# poiduino7_7.net
KiCad netlist of a schematic drawn in EAGLE
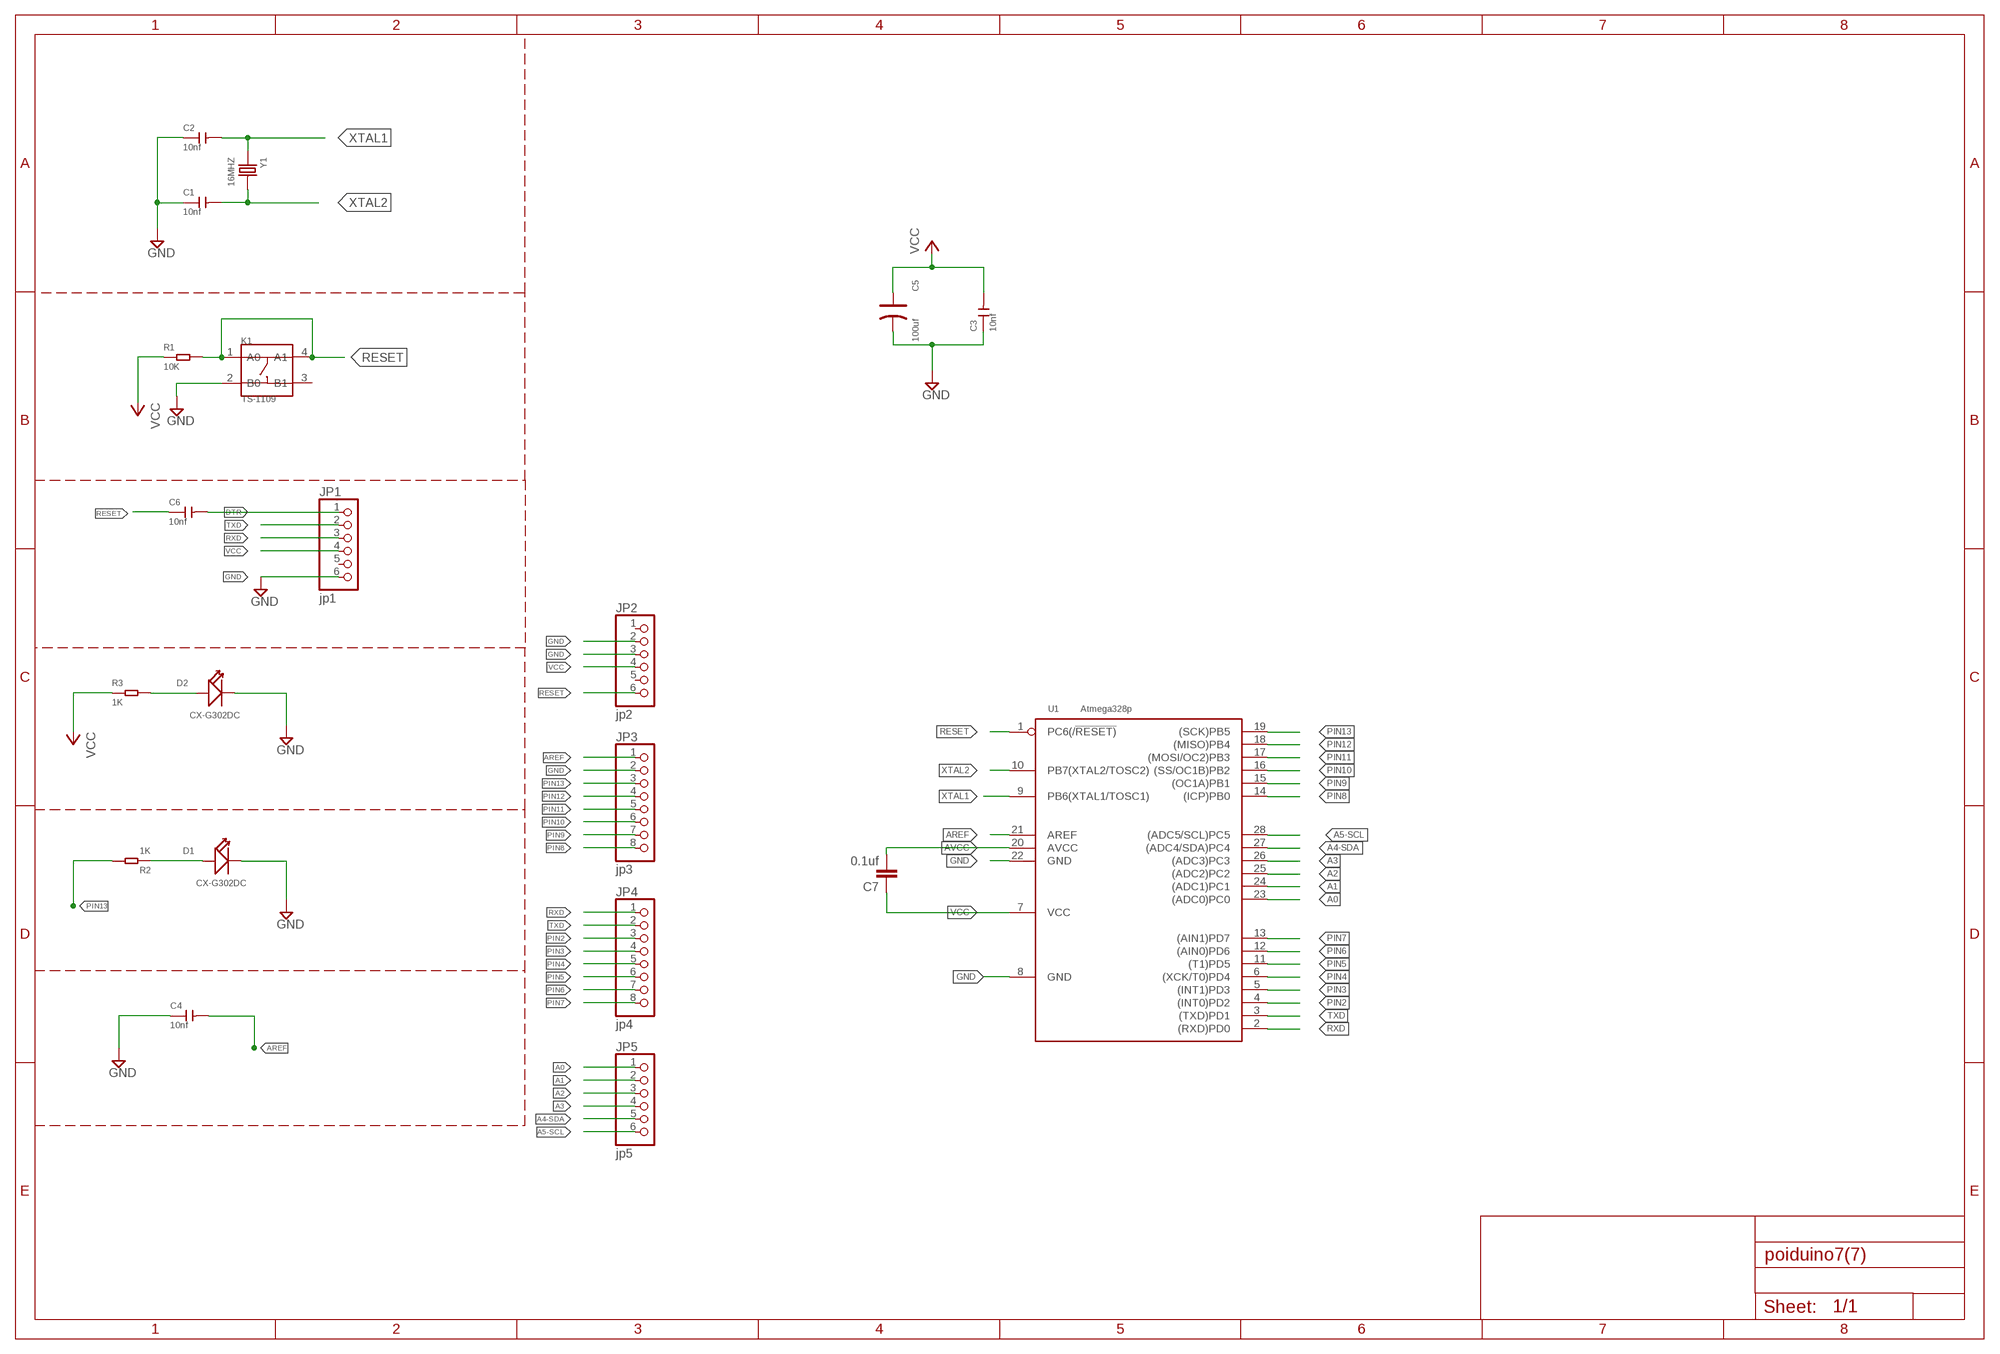
[diagram p0: schematic, sheet 1]

(export (version "E")
  (design (tool "Eeschema 10.0.6"))
  (components
    (comp (ref "C1")
      (value "10nf")
      (footprint "eagle-import:CERAMIC-2.54")
      (libsource (lib "eagle-import") (part "DIP-CERAMIC-DISC-10NF-50V-Y5V(D4.0MM)"))
    )
    (comp (ref "C2")
      (value "10nf")
      (footprint "eagle-import:CERAMIC-2.54")
      (libsource (lib "eagle-import") (part "DIP-CERAMIC-DISC-10NF-50V-Y5V(D4.0MM)"))
    )
    (comp (ref "C3")
      (value "10nf")
      (footprint "eagle-import:CERAMIC-2.54")
      (libsource (lib "eagle-import") (part "DIP-CERAMIC-DISC-10NF-50V-Y5V(D4.0MM)"))
    )
    (comp (ref "C4")
      (value "10nf")
      (footprint "eagle-import:CERAMIC-2.54")
      (libsource (lib "eagle-import") (part "DIP-CERAMIC-DISC-10NF-50V-Y5V(D4.0MM)"))
    )
    (comp (ref "C5")
      (value "100uf")
      (footprint "eagle-import:PC-D5.3MM")
      (fields (field (name "MPN") "KS 100uF/16V"))
      (libsource (lib "eagle-import") (part "DIP-ALUMINUM-47UF-16V(D5-H7MM)"))
    )
    (comp (ref "C6")
      (value "10nf")
      (footprint "eagle-import:CERAMIC-2.54")
      (libsource (lib "eagle-import") (part "DIP-CERAMIC-DISC-10NF-50V-Y5V(D4.0MM)"))
    )
    (comp (ref "C7")
      (value "0.1uf")
      (footprint "eagle-import:C5B2.5")
      (libsource (lib "eagle-import") (part "C5/2.5"))
    )
    (comp (ref "D1")
      (value "CX-G302DC")
      (footprint "eagle-import:LED2-2.54-D3.0MM")
      (libsource (lib "eagle-import") (part "DIP-LED-GREEN-GREEN(2P-D3MM)"))
    )
    (comp (ref "D2")
      (value "CX-G302DC")
      (footprint "eagle-import:LED2-2.54-D3.0MM")
      (libsource (lib "eagle-import") (part "DIP-LED-GREEN-GREEN(2P-D3MM)"))
    )
    (comp (ref "JP1")
      (value "jp1")
      (footprint "eagle-import:1X06")
      (libsource (lib "eagle-import") (part "PINHD-1X6"))
    )
    (comp (ref "JP2")
      (value "jp2")
      (footprint "eagle-import:1X06")
      (libsource (lib "eagle-import") (part "PINHD-1X6"))
    )
    (comp (ref "JP3")
      (value "jp3")
      (footprint "eagle-import:1X08")
      (libsource (lib "eagle-import") (part "PINHD-1X8"))
    )
    (comp (ref "JP4")
      (value "jp4")
      (footprint "eagle-import:1X08")
      (libsource (lib "eagle-import") (part "PINHD-1X8"))
    )
    (comp (ref "JP5")
      (value "jp5")
      (footprint "eagle-import:1X06")
      (libsource (lib "eagle-import") (part "PINHD-1X6"))
    )
    (comp (ref "K1")
      (value "TS-1109")
      (footprint "eagle-import:SW4-6.0X6.0X5.0MM")
      (libsource (lib "eagle-import") (part "DIP-BUTTON-4P"))
    )
    (comp (ref "R1")
      (value "10K")
      (footprint "eagle-import:PR-D2.3XL6.5MM")
      (fields (field (name "MPN") "FHCFR-1/4W-103J"))
      (libsource (lib "eagle-import") (part "DIP-RES-10K-5%-1/4W(PR-D2.3XL6.5MM)"))
    )
    (comp (ref "R2")
      (value "1K")
      (footprint "eagle-import:PR-D2.3XL6.5MM")
      (fields (field (name "MPN") "FHCFR-1/4W-102J"))
      (libsource (lib "eagle-import") (part "DIP-RES-1K-5%-1/4W(PR-D2.3XL6.5MM)"))
    )
    (comp (ref "R3")
      (value "1K")
      (footprint "eagle-import:PR-D2.3XL6.5MM")
      (fields (field (name "MPN") "FHCFR-1/4W-102J"))
      (libsource (lib "eagle-import") (part "DIP-RES-1K-5%-1/4W(PR-D2.3XL6.5MM)"))
    )
    (comp (ref "U1")
      (value "Atmega328p")
      (footprint "eagle-import:DIP28-2.54-34.7X7.62MM")
      (fields (field (name "MPN") "ATMEGA328P-PU"))
      (libsource (lib "eagle-import") (part "MCU-ATMEGA328P-PU(DIP28)"))
    )
    (comp (ref "Y1")
      (value "16MHZ")
      (footprint "eagle-import:HC49US")
      (fields (field (name "MPN") "HC-49US    16.000MHz"))
      (libsource (lib "eagle-import") (part "DIP-CRYSTAL-16MHZ-18PF-30PPM-40R(HC49US)"))
    )
  )
  (nets
    (net (code "1") (name "A0") (class "Default")
      (node (ref "JP5") (pin "1") (pinfunction "1_1") (pintype "passive"))
      (node (ref "U1") (pin "23") (pinfunction "(ADC0)PC0_23") (pintype "bidirectional"))
    )
    (net (code "2") (name "A1") (class "Default")
      (node (ref "JP5") (pin "2") (pinfunction "2_2") (pintype "passive"))
      (node (ref "U1") (pin "24") (pinfunction "(ADC1)PC1_24") (pintype "bidirectional"))
    )
    (net (code "3") (name "A2") (class "Default")
      (node (ref "JP5") (pin "3") (pinfunction "3_3") (pintype "passive"))
      (node (ref "U1") (pin "25") (pinfunction "(ADC2)PC2_25") (pintype "bidirectional"))
    )
    (net (code "4") (name "A3") (class "Default")
      (node (ref "JP5") (pin "4") (pinfunction "4_4") (pintype "passive"))
      (node (ref "U1") (pin "26") (pinfunction "(ADC3)PC3_26") (pintype "bidirectional"))
    )
    (net (code "5") (name "A4-SDA") (class "Default")
      (node (ref "JP5") (pin "5") (pinfunction "5_5") (pintype "passive"))
      (node (ref "U1") (pin "27") (pinfunction "(ADC4/SDA)PC4_27") (pintype "bidirectional"))
    )
    (net (code "6") (name "A5-SCL") (class "Default")
      (node (ref "JP5") (pin "6") (pinfunction "6_6") (pintype "passive"))
      (node (ref "U1") (pin "28") (pinfunction "(ADC5/SCL)PC5_28") (pintype "bidirectional"))
    )
    (net (code "7") (name "AREF") (class "Default")
      (node (ref "C4") (pin "2") (pinfunction "2_2") (pintype "passive"))
      (node (ref "JP3") (pin "1") (pinfunction "1_1") (pintype "passive"))
      (node (ref "U1") (pin "21") (pinfunction "AREF_21") (pintype "bidirectional"))
    )
    (net (code "8") (name "AVCC") (class "Default")
      (node (ref "C7") (pin "2") (pinfunction "2_2") (pintype "passive"))
      (node (ref "U1") (pin "20") (pinfunction "AVCC_20") (pintype "bidirectional"))
    )
    (net (code "9") (name "DTR") (class "Default")
      (node (ref "C6") (pin "2") (pinfunction "2_2") (pintype "passive"))
      (node (ref "JP1") (pin "1") (pinfunction "1_1") (pintype "passive"))
    )
    (net (code "10") (name "GND") (class "Default")
      (node (ref "C1") (pin "1") (pinfunction "1_1") (pintype "passive"))
      (node (ref "C2") (pin "1") (pinfunction "1_1") (pintype "passive"))
      (node (ref "C3") (pin "1") (pinfunction "1_1") (pintype "passive"))
      (node (ref "C4") (pin "1") (pinfunction "1_1") (pintype "passive"))
      (node (ref "C5") (pin "-") (pinfunction "-_-") (pintype "passive"))
      (node (ref "D1") (pin "K") (pinfunction "-_K") (pintype "passive"))
      (node (ref "D2") (pin "K") (pinfunction "-_K") (pintype "passive"))
      (node (ref "JP1") (pin "6") (pinfunction "6_6") (pintype "passive"))
      (node (ref "JP2") (pin "2") (pinfunction "2_2") (pintype "passive"))
      (node (ref "JP2") (pin "3") (pinfunction "3_3") (pintype "passive"))
      (node (ref "JP3") (pin "2") (pinfunction "2_2") (pintype "passive"))
      (node (ref "K1") (pin "2") (pinfunction "B0_2") (pintype "bidirectional"))
      (node (ref "U1") (pin "22") (pinfunction "GND_22") (pintype "bidirectional"))
      (node (ref "U1") (pin "8") (pinfunction "GND_8") (pintype "bidirectional"))
    )
    (net (code "11") (name "Net-(D1-+)") (class "Default")
      (node (ref "D1") (pin "A") (pinfunction "+_A") (pintype "passive"))
      (node (ref "R2") (pin "1") (pinfunction "1_1") (pintype "passive"))
    )
    (net (code "12") (name "Net-(D2-+)") (class "Default")
      (node (ref "D2") (pin "A") (pinfunction "+_A") (pintype "passive"))
      (node (ref "R3") (pin "2") (pinfunction "2_2") (pintype "passive"))
    )
    (net (code "13") (name "PIN2") (class "Default")
      (node (ref "JP4") (pin "3") (pinfunction "3_3") (pintype "passive"))
      (node (ref "U1") (pin "4") (pinfunction "(INT0)PD2_4") (pintype "bidirectional"))
    )
    (net (code "14") (name "PIN3") (class "Default")
      (node (ref "JP4") (pin "4") (pinfunction "4_4") (pintype "passive"))
      (node (ref "U1") (pin "5") (pinfunction "(INT1)PD3_5") (pintype "bidirectional"))
    )
    (net (code "15") (name "PIN4") (class "Default")
      (node (ref "JP4") (pin "5") (pinfunction "5_5") (pintype "passive"))
      (node (ref "U1") (pin "6") (pinfunction "(XCK/T0)PD4_6") (pintype "bidirectional"))
    )
    (net (code "16") (name "PIN5") (class "Default")
      (node (ref "JP4") (pin "6") (pinfunction "6_6") (pintype "passive"))
      (node (ref "U1") (pin "11") (pinfunction "(T1)PD5_11") (pintype "bidirectional"))
    )
    (net (code "17") (name "PIN6") (class "Default")
      (node (ref "JP4") (pin "7") (pinfunction "7_7") (pintype "passive"))
      (node (ref "U1") (pin "12") (pinfunction "(AIN0)PD6_12") (pintype "bidirectional"))
    )
    (net (code "18") (name "PIN7") (class "Default")
      (node (ref "JP4") (pin "8") (pinfunction "8_8") (pintype "passive"))
      (node (ref "U1") (pin "13") (pinfunction "(AIN1)PD7_13") (pintype "bidirectional"))
    )
    (net (code "19") (name "PIN8") (class "Default")
      (node (ref "JP3") (pin "8") (pinfunction "8_8") (pintype "passive"))
      (node (ref "U1") (pin "14") (pinfunction "(ICP)PB0_14") (pintype "bidirectional"))
    )
    (net (code "20") (name "PIN9") (class "Default")
      (node (ref "JP3") (pin "7") (pinfunction "7_7") (pintype "passive"))
      (node (ref "U1") (pin "15") (pinfunction "(OC1A)PB1_15") (pintype "bidirectional"))
    )
    (net (code "21") (name "PIN10") (class "Default")
      (node (ref "JP3") (pin "6") (pinfunction "6_6") (pintype "passive"))
      (node (ref "U1") (pin "16") (pinfunction "(SS/OC1B)PB2_16") (pintype "bidirectional"))
    )
    (net (code "22") (name "PIN11") (class "Default")
      (node (ref "JP3") (pin "5") (pinfunction "5_5") (pintype "passive"))
      (node (ref "U1") (pin "17") (pinfunction "(MOSI/OC2)PB3_17") (pintype "bidirectional"))
    )
    (net (code "23") (name "PIN12") (class "Default")
      (node (ref "JP3") (pin "4") (pinfunction "4_4") (pintype "passive"))
      (node (ref "U1") (pin "18") (pinfunction "(MISO)PB4_18") (pintype "bidirectional"))
    )
    (net (code "24") (name "PIN13") (class "Default")
      (node (ref "JP3") (pin "3") (pinfunction "3_3") (pintype "passive"))
      (node (ref "R2") (pin "2") (pinfunction "2_2") (pintype "passive"))
      (node (ref "U1") (pin "19") (pinfunction "(SCK)PB5_19") (pintype "bidirectional"))
    )
    (net (code "25") (name "RESET") (class "Default")
      (node (ref "C6") (pin "1") (pinfunction "1_1") (pintype "passive"))
      (node (ref "JP2") (pin "6") (pinfunction "6_6") (pintype "passive"))
      (node (ref "K1") (pin "1") (pinfunction "A0_1") (pintype "bidirectional"))
      (node (ref "K1") (pin "4") (pinfunction "A1_4") (pintype "bidirectional"))
      (node (ref "R1") (pin "2") (pinfunction "2_2") (pintype "passive"))
      (node (ref "U1") (pin "1") (pinfunction "PC6(/~{RESET})_1") (pintype "bidirectional"))
    )
    (net (code "26") (name "RXD") (class "Default")
      (node (ref "JP1") (pin "3") (pinfunction "3_3") (pintype "passive"))
      (node (ref "JP4") (pin "1") (pinfunction "1_1") (pintype "passive"))
      (node (ref "U1") (pin "2") (pinfunction "(RXD)PD0_2") (pintype "bidirectional"))
    )
    (net (code "27") (name "TXD") (class "Default")
      (node (ref "JP1") (pin "2") (pinfunction "2_2") (pintype "passive"))
      (node (ref "JP4") (pin "2") (pinfunction "2_2") (pintype "passive"))
      (node (ref "U1") (pin "3") (pinfunction "(TXD)PD1_3") (pintype "bidirectional"))
    )
    (net (code "28") (name "VCC") (class "Default")
      (node (ref "C3") (pin "2") (pinfunction "2_2") (pintype "passive"))
      (node (ref "C5") (pin "+") (pinfunction "+_+") (pintype "passive"))
      (node (ref "C7") (pin "1") (pinfunction "1_1") (pintype "passive"))
      (node (ref "JP1") (pin "4") (pinfunction "4_4") (pintype "passive"))
      (node (ref "JP2") (pin "4") (pinfunction "4_4") (pintype "passive"))
      (node (ref "R1") (pin "1") (pinfunction "1_1") (pintype "passive"))
      (node (ref "R3") (pin "1") (pinfunction "1_1") (pintype "passive"))
      (node (ref "U1") (pin "7") (pinfunction "VCC_7") (pintype "bidirectional"))
    )
    (net (code "29") (name "XTAL1") (class "Default")
      (node (ref "C2") (pin "2") (pinfunction "2_2") (pintype "passive"))
      (node (ref "U1") (pin "9") (pinfunction "PB6(XTAL1/TOSC1)_9") (pintype "bidirectional"))
      (node (ref "Y1") (pin "1") (pinfunction "1_1") (pintype "passive"))
    )
    (net (code "30") (name "XTAL2") (class "Default")
      (node (ref "C1") (pin "2") (pinfunction "2_2") (pintype "passive"))
      (node (ref "U1") (pin "10") (pinfunction "PB7(XTAL2/TOSC2)_10") (pintype "bidirectional"))
      (node (ref "Y1") (pin "2") (pinfunction "2_2") (pintype "passive"))
    )
    (net (code "31") (name "unconnected-(JP1-Pad5)") (class "Default")
      (node (ref "JP1") (pin "5") (pinfunction "5_5") (pintype "passive"))
    )
    (net (code "32") (name "unconnected-(JP2-Pad1)") (class "Default")
      (node (ref "JP2") (pin "1") (pinfunction "1_1") (pintype "passive"))
    )
    (net (code "33") (name "unconnected-(JP2-Pad5)") (class "Default")
      (node (ref "JP2") (pin "5") (pinfunction "5_5") (pintype "passive"))
    )
    (net (code "34") (name "unconnected-(K1-B1-Pad3)") (class "Default")
      (node (ref "K1") (pin "3") (pinfunction "B1_3") (pintype "bidirectional"))
    )
  )
)
